# mptt-controller.net
KiCad netlist of a schematic drawn in EAGLE
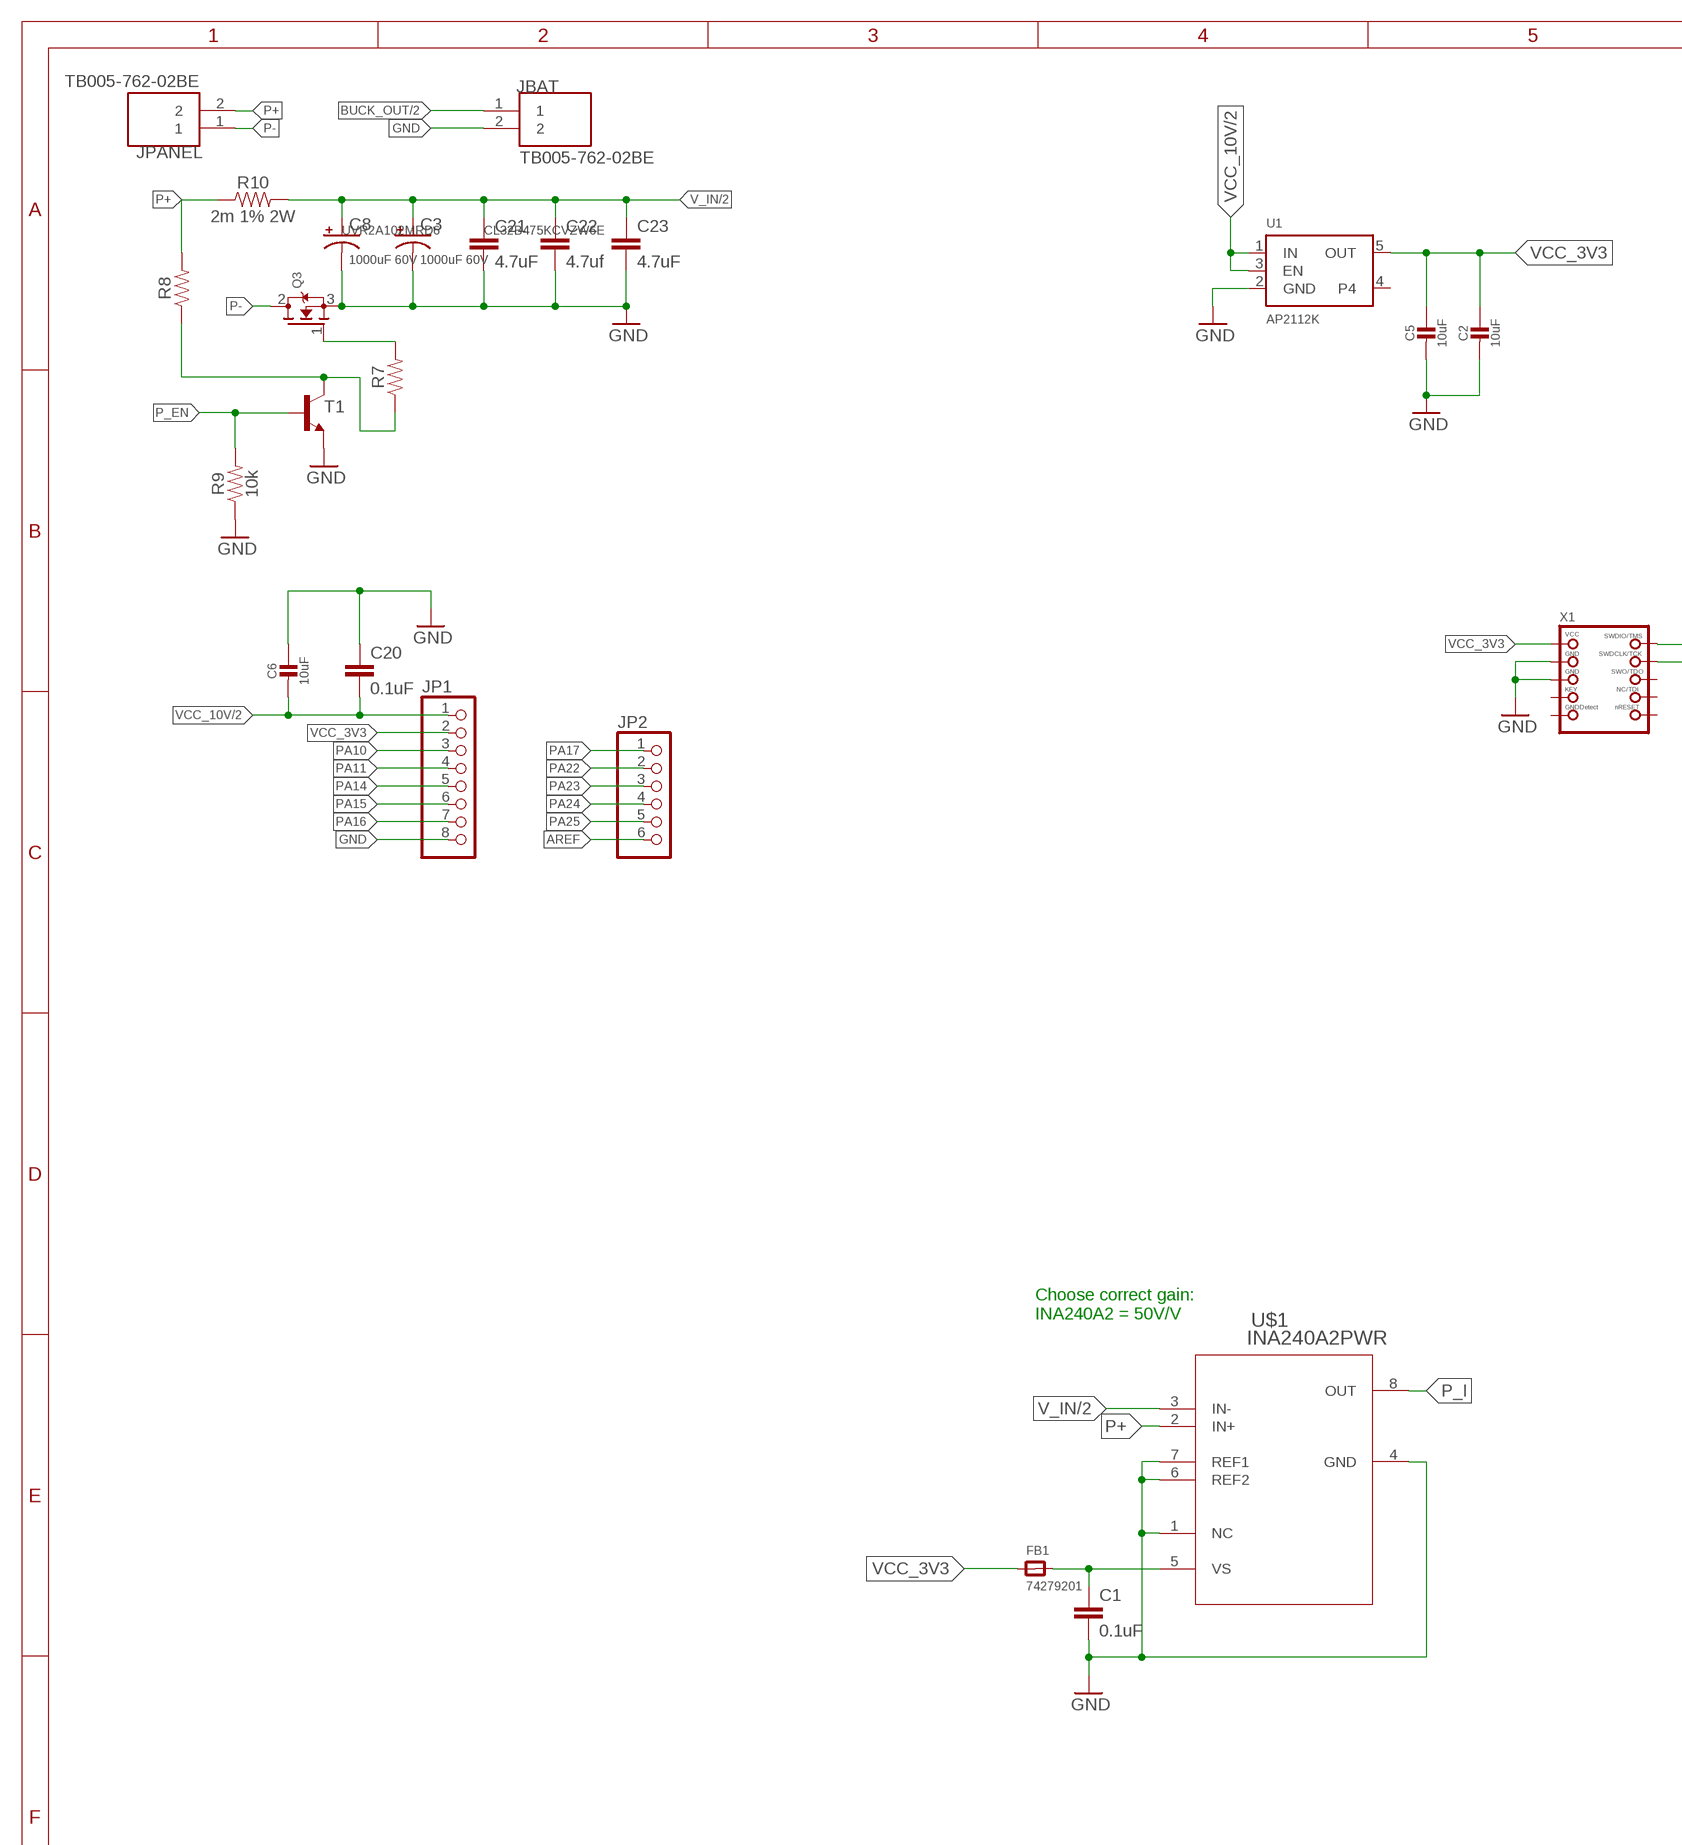
[diagram p0: schematic, sheet 1, part 1 of 2]
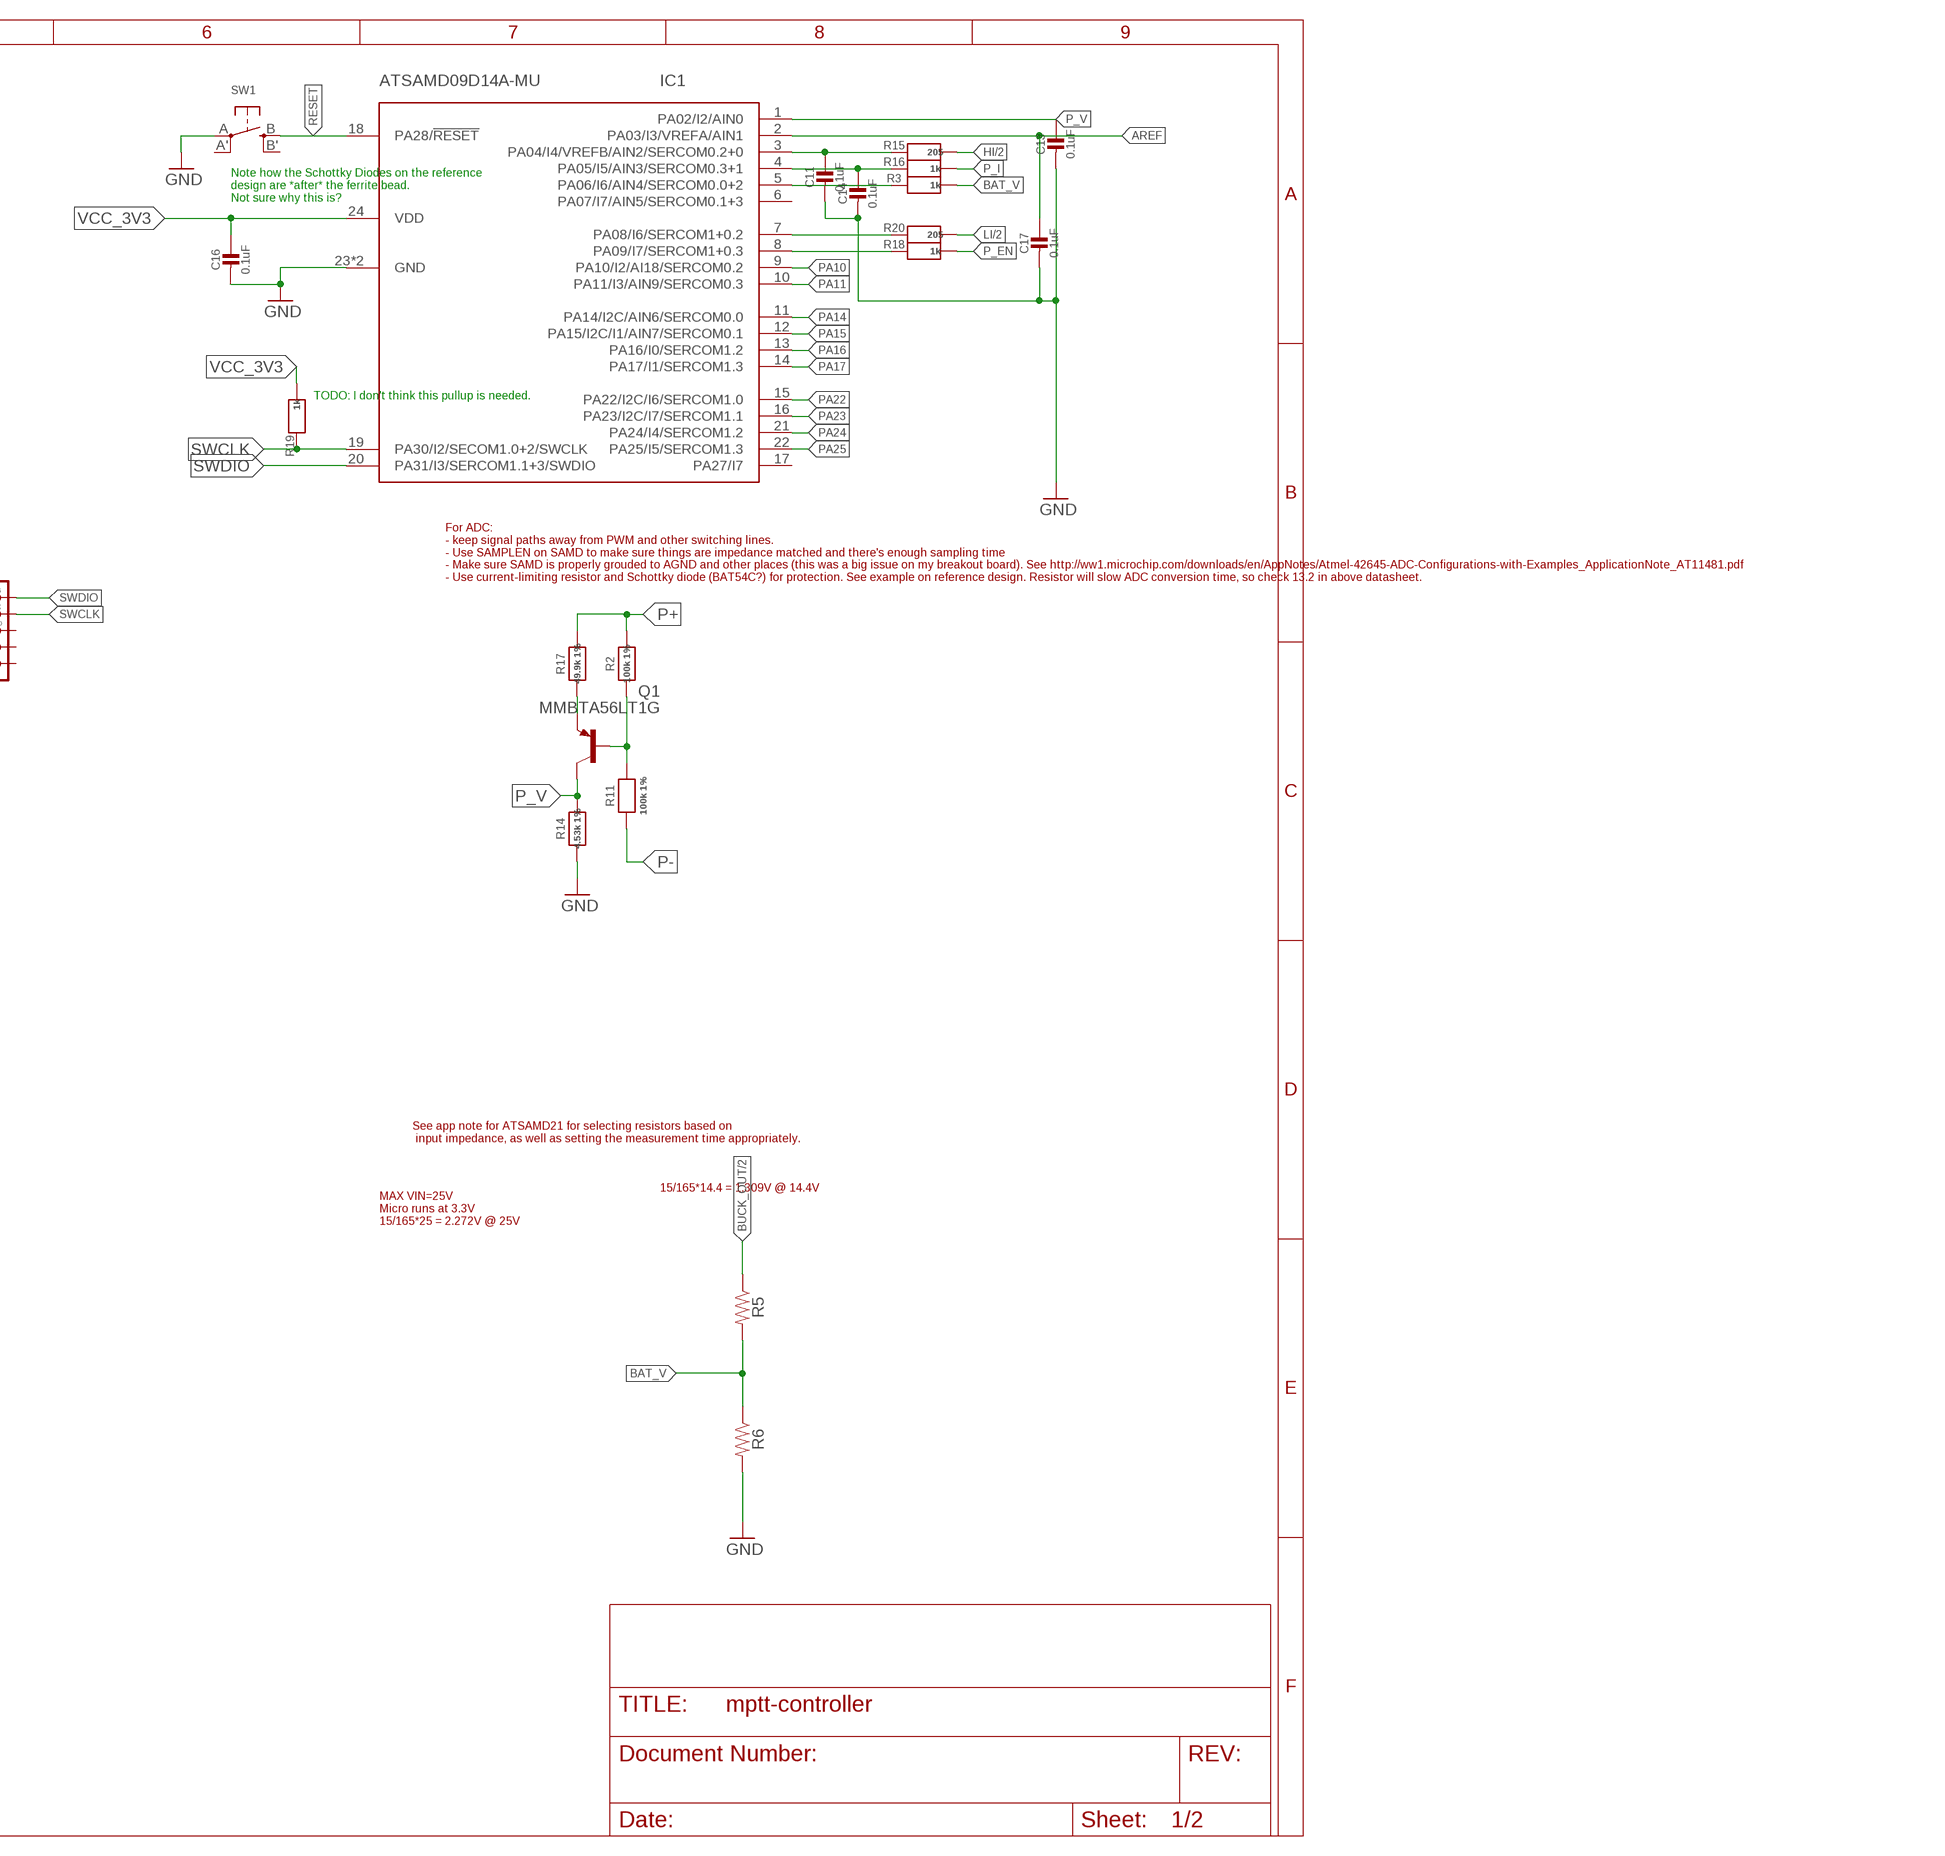
[diagram p1: schematic, sheet 1, part 2 of 2]
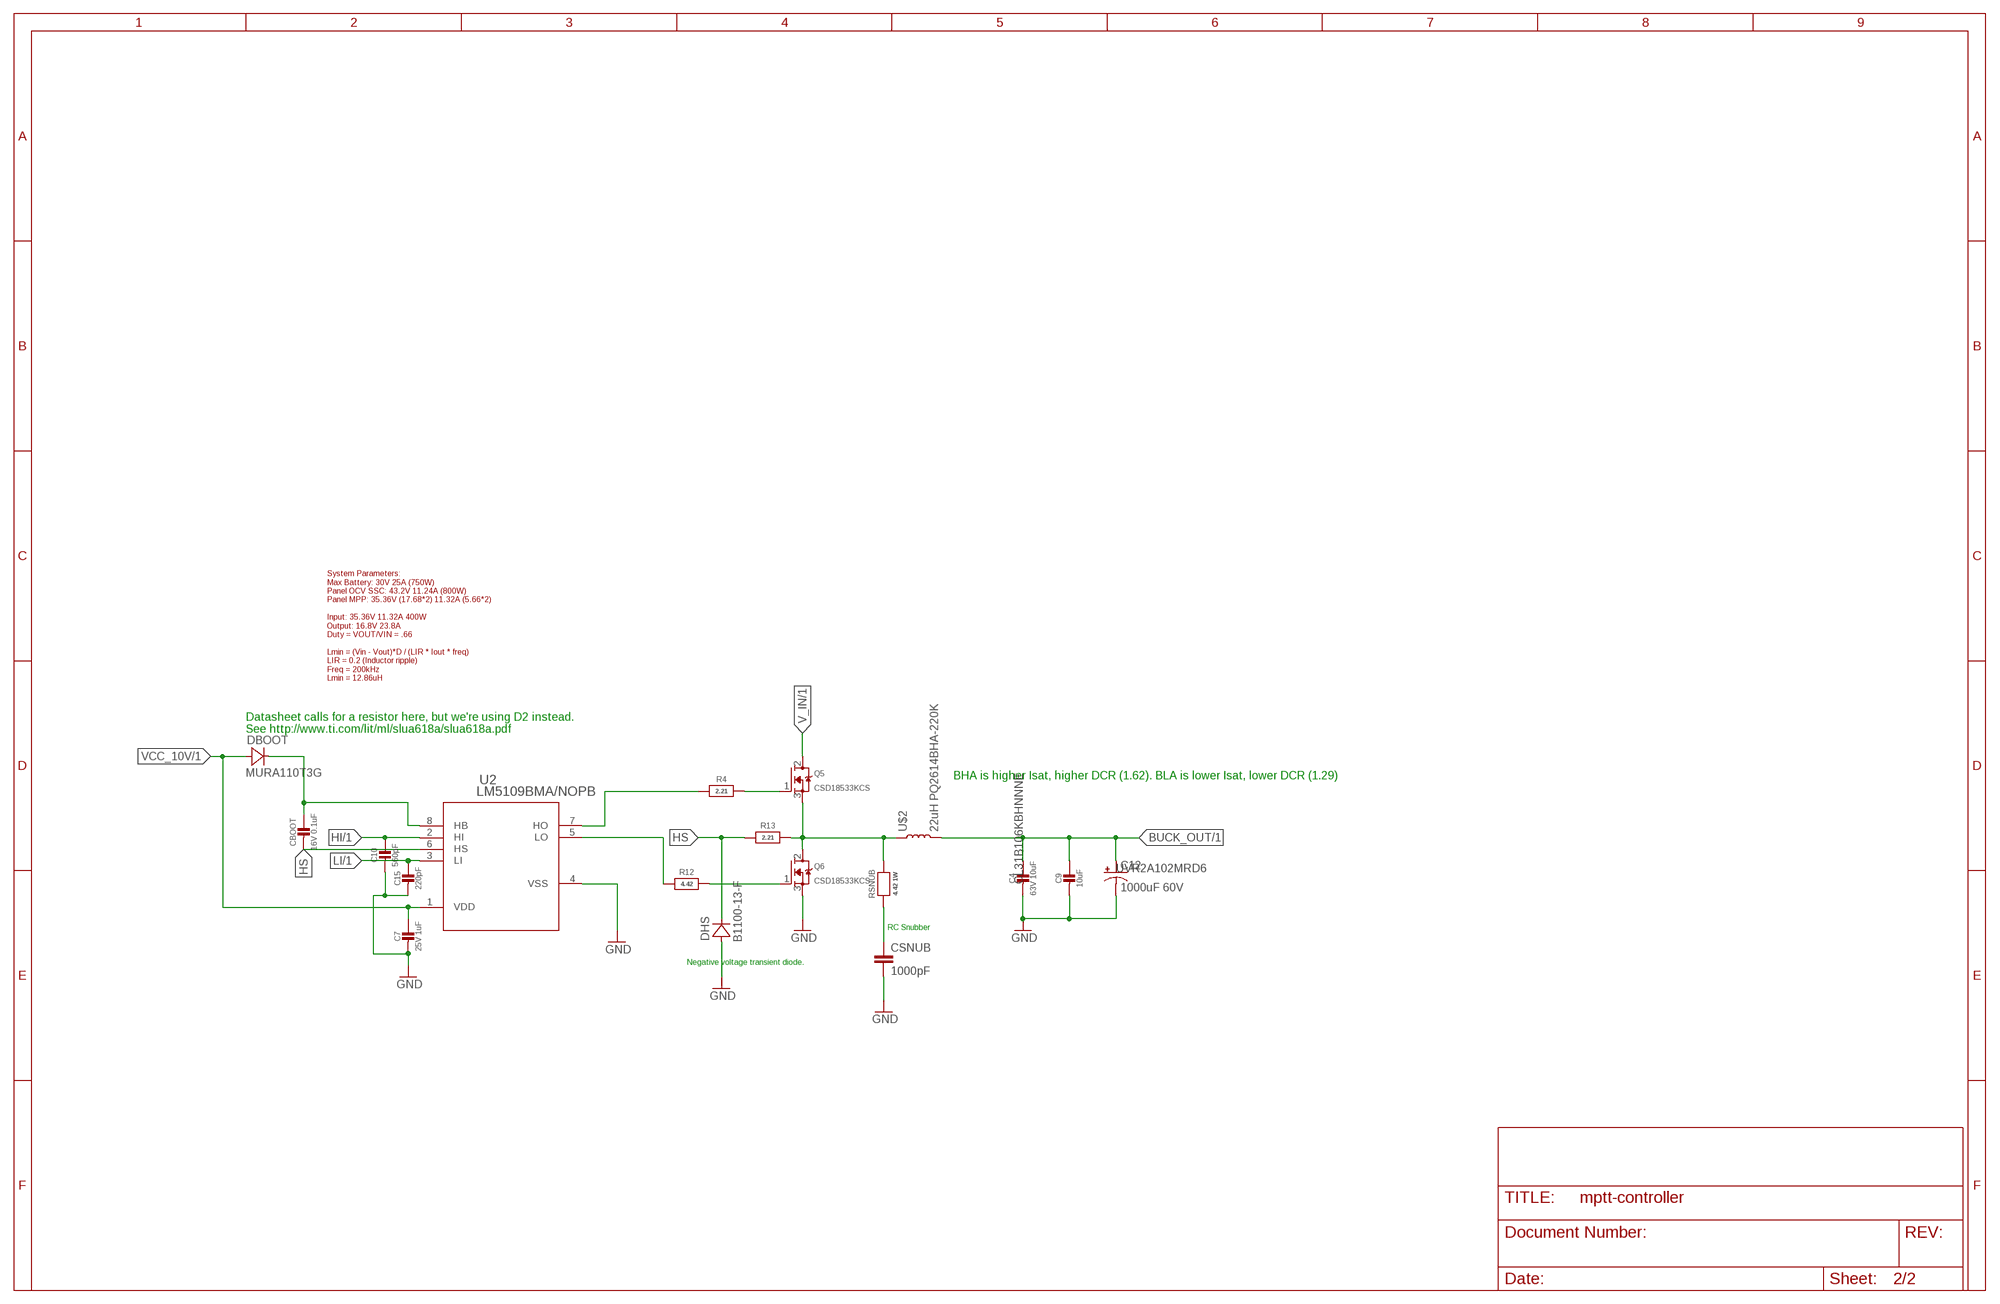
[diagram p2: schematic, sheet 2]

(export (version "E")
  (design (tool "Eeschema 10.0.6"))
  (components
    (comp (ref "C4")
      (value "63V 10uF")
      (footprint "eagle-import:_1206")
      (fields (field (name "PN") "CL31B106KBHNNNE"))
      (libsource (lib "eagle-import") (part "CAP_CERAMIC_1206"))
    )
    (comp (ref "C7")
      (value "25V 1uF")
      (footprint "eagle-import:_0805")
      (libsource (lib "eagle-import") (part "CAP_CERAMIC_0805"))
    )
    (comp (ref "C9")
      (value "10uF")
      (footprint "eagle-import:_1206")
      (libsource (lib "eagle-import") (part "CAP_CERAMIC_1206"))
    )
    (comp (ref "C10")
      (value "560pF")
      (footprint "eagle-import:_0603")
      (libsource (lib "eagle-import") (part "Adafruit Metro M0 Express_CAP_CERAMIC_0603"))
    )
    (comp (ref "C12")
      (value "1000uF 60V")
      (footprint "eagle-import:CPOL-RADIAL-1000UF-25V")
      (fields (field (name "PARTNUM") "UVR2A102MRD6"))
      (libsource (lib "eagle-import") (part "CAP_POLPTH4"))
    )
    (comp (ref "C15")
      (value "220pF")
      (footprint "eagle-import:_0603")
      (libsource (lib "eagle-import") (part "Adafruit Metro M0 Express_CAP_CERAMIC_0603"))
    )
    (comp (ref "CBOOT")
      (value "16V 0.1uF")
      (footprint "eagle-import:_0805")
      (libsource (lib "eagle-import") (part "CAP_CERAMIC_0805"))
    )
    (comp (ref "CSNUB")
      (value "1000pF")
      (footprint "eagle-import:0603-CAP")
      (libsource (lib "eagle-import") (part "0.1UF-25V(+80/-20%)(0603)"))
    )
    (comp (ref "DBOOT")
      (value "MURA110T3G")
      (footprint "eagle-import:SMA")
      (libsource (lib "eagle-import") (part "MBRA340T3"))
    )
    (comp (ref "DHS")
      (value "B1100-13-F")
      (footprint "eagle-import:SMA")
      (libsource (lib "eagle-import") (part "MBRA340T3"))
    )
    (comp (ref "Q5")
      (value "CSD18533KCS")
      (footprint "eagle-import:TO220V")
      (libsource (lib "eagle-import") (part "MOSFET-NGDS_TO220V"))
    )
    (comp (ref "Q6")
      (value "CSD18533KCS")
      (footprint "eagle-import:TO220V")
      (libsource (lib "eagle-import") (part "MOSFET-NGDS_TO220V"))
    )
    (comp (ref "R4")
      (value "2.21")
      (footprint "eagle-import:_0805")
      (libsource (lib "eagle-import") (part "Adafruit Metro M0 Express_RESISTOR_0805"))
    )
    (comp (ref "R12")
      (value "4.42")
      (footprint "eagle-import:_0805")
      (libsource (lib "eagle-import") (part "Adafruit Metro M0 Express_RESISTOR_0805"))
    )
    (comp (ref "R13")
      (value "2.21")
      (footprint "eagle-import:_0805")
      (libsource (lib "eagle-import") (part "Adafruit Metro M0 Express_RESISTOR_0805"))
    )
    (comp (ref "RSNUB")
      (value "4.42 1W")
      (footprint "eagle-import:2512")
      (libsource (lib "eagle-import") (part "Adafruit Metro M0 Express_RESISTOR2512"))
    )
    (comp (ref "U$2")
      (value "22uH PQ2614BHA-220K")
      (footprint "eagle-import:PQ2614")
      (libsource (lib "eagle-import") (part "PQ2614"))
    )
    (comp (ref "U2")
      (value "LM5109BMA/NOPB")
      (footprint "eagle-import:M08A_TEX")
      (fields (field (name "COPYRIGHT") "Copyright (C) 2018 Accelerated Designs. All rights reserved"))
      (libsource (lib "eagle-import") (part "LM5109BMA/NOPB"))
    )
    (comp (ref "C1")
      (value "0.1uF")
      (footprint "eagle-import:0603-CAP")
      (libsource (lib "eagle-import") (part "0.1UF-25V(+80/-20%)(0603)"))
    )
    (comp (ref "C2")
      (value "10uF")
      (footprint "eagle-import:_0805")
      (libsource (lib "eagle-import") (part "CAP_CERAMIC_0805"))
    )
    (comp (ref "C3")
      (value "1000uF 60V")
      (footprint "eagle-import:CPOL-RADIAL-1000UF-25V")
      (libsource (lib "eagle-import") (part "CAP_POLPTH4"))
    )
    (comp (ref "C5")
      (value "10uF")
      (footprint "eagle-import:_0805")
      (libsource (lib "eagle-import") (part "CAP_CERAMIC_0805"))
    )
    (comp (ref "C6")
      (value "10uF")
      (footprint "eagle-import:_0805")
      (libsource (lib "eagle-import") (part "CAP_CERAMIC_0805"))
    )
    (comp (ref "C8")
      (value "1000uF 60V")
      (footprint "eagle-import:CPOL-RADIAL-1000UF-25V")
      (fields (field (name "PARTNUM") "UVR2A102MRD6"))
      (libsource (lib "eagle-import") (part "CAP_POLPTH4"))
    )
    (comp (ref "C11")
      (value "0.1uF")
      (footprint "eagle-import:_0402MP")
      (libsource (lib "eagle-import") (part "CAP_CERAMIC_0402MP"))
    )
    (comp (ref "C13")
      (value "0.1uF")
      (footprint "eagle-import:_0402MP")
      (libsource (lib "eagle-import") (part "CAP_CERAMIC_0402MP"))
    )
    (comp (ref "C14")
      (value "0.1uF")
      (footprint "eagle-import:_0402MP")
      (libsource (lib "eagle-import") (part "CAP_CERAMIC_0402MP"))
    )
    (comp (ref "C16")
      (value "0.1uF")
      (footprint "eagle-import:_0402MP")
      (libsource (lib "eagle-import") (part "CAP_CERAMIC_0402MP"))
    )
    (comp (ref "C17")
      (value "0.1uF")
      (footprint "eagle-import:_0402MP")
      (libsource (lib "eagle-import") (part "CAP_CERAMIC_0402MP"))
    )
    (comp (ref "C20")
      (value "0.1uF")
      (footprint "eagle-import:0603-CAP")
      (libsource (lib "eagle-import") (part "0.1UF-25V(+80/-20%)(0603)"))
    )
    (comp (ref "C21")
      (value "4.7uF")
      (footprint "eagle-import:C1210")
      (fields (field (name "PARTNUM") "CL32B475KCVZW6E"))
      (libsource (lib "eagle-import") (part "C-EUC1210"))
    )
    (comp (ref "C22")
      (value "4.7uf")
      (footprint "eagle-import:C1210")
      (libsource (lib "eagle-import") (part "C-EUC1210"))
    )
    (comp (ref "C23")
      (value "4.7uF")
      (footprint "eagle-import:C1210")
      (libsource (lib "eagle-import") (part "C-EUC1210"))
    )
    (comp (ref "FB1")
      (value "74279201")
      (footprint "eagle-import:_0805")
      (libsource (lib "eagle-import") (part "FERRITE_0805"))
    )
    (comp (ref "IC1")
      (value "ATSAMD09D14A-MU")
      (footprint "eagle-import:QFN24_4MM")
      (libsource (lib "eagle-import") (part "ATSAMD09D14A-MU"))
    )
    (comp (ref "JBAT")
      (value "TB005-762-02BE")
      (footprint "eagle-import:CUI_TB005-762-02BE")
      (fields (field (name "MANUFACTURER") "CUI"))
      (libsource (lib "eagle-import") (part "TB005-762-02BE"))
    )
    (comp (ref "JP1")
      (value "HEADER-1X8ROUND")
      (footprint "eagle-import:1X08_ROUND")
      (libsource (lib "eagle-import") (part "HEADER-1X8ROUND"))
    )
    (comp (ref "JP2")
      (value "HEADER-1X6ROUND")
      (footprint "eagle-import:1X06_ROUND")
      (libsource (lib "eagle-import") (part "HEADER-1X6ROUND"))
    )
    (comp (ref "JPANEL")
      (value "TB005-762-02BE")
      (footprint "eagle-import:CUI_TB005-762-02BE")
      (fields (field (name "MANUFACTURER") "CUI"))
      (libsource (lib "eagle-import") (part "TB005-762-02BE"))
    )
    (comp (ref "Q1")
      (value "MMBTA56LT1G")
      (footprint "eagle-import:SOT23-BEC")
      (libsource (lib "eagle-import") (part "MMBTA92SMDLT1"))
    )
    (comp (ref "Q3")
      (value "MOSFET-NGDS_TO220V")
      (footprint "eagle-import:TO220V")
      (libsource (lib "eagle-import") (part "MOSFET-NGDS_TO220V"))
    )
    (comp (ref "R2")
      (value "100k 1%")
      (footprint "eagle-import:_0805MP")
      (libsource (lib "eagle-import") (part "Adafruit Metro M0 Express_RESISTOR_0805MP"))
    )
    (comp (ref "R3")
      (value "1k")
      (footprint "eagle-import:_0402MP")
      (libsource (lib "eagle-import") (part "RESISTOR_0402MP"))
    )
    (comp (ref "R5")
      (value "RESISTOR0603")
      (footprint "eagle-import:0603")
      (libsource (lib "eagle-import") (part "RESISTOR0603"))
    )
    (comp (ref "R6")
      (value "RESISTOR0603")
      (footprint "eagle-import:0603")
      (libsource (lib "eagle-import") (part "RESISTOR0603"))
    )
    (comp (ref "R7")
      (value "RESISTOR0603")
      (footprint "eagle-import:0603")
      (libsource (lib "eagle-import") (part "RESISTOR0603"))
    )
    (comp (ref "R8")
      (value "RESISTOR0603")
      (footprint "eagle-import:0603")
      (libsource (lib "eagle-import") (part "RESISTOR0603"))
    )
    (comp (ref "R9")
      (value "10k")
      (footprint "eagle-import:0603")
      (libsource (lib "eagle-import") (part "RESISTOR0603"))
    )
    (comp (ref "R10")
      (value "2m 1% 2W")
      (footprint "eagle-import:2512")
      (libsource (lib "eagle-import") (part "0.05OHM-2512-3W-1%"))
    )
    (comp (ref "R11")
      (value "100k 1%")
      (footprint "eagle-import:_0805MP")
      (libsource (lib "eagle-import") (part "Adafruit Metro M0 Express_RESISTOR_0805MP"))
    )
    (comp (ref "R14")
      (value "4.53k 1%")
      (footprint "eagle-import:_0805MP")
      (libsource (lib "eagle-import") (part "Adafruit Metro M0 Express_RESISTOR_0805MP"))
    )
    (comp (ref "R15")
      (value "205")
      (footprint "eagle-import:_0402MP")
      (libsource (lib "eagle-import") (part "RESISTOR_0402MP"))
    )
    (comp (ref "R16")
      (value "1k")
      (footprint "eagle-import:_0402MP")
      (libsource (lib "eagle-import") (part "RESISTOR_0402MP"))
    )
    (comp (ref "R17")
      (value "49.9k 1%")
      (footprint "eagle-import:_0805MP")
      (libsource (lib "eagle-import") (part "Adafruit Metro M0 Express_RESISTOR_0805MP"))
    )
    (comp (ref "R18")
      (value "1k")
      (footprint "eagle-import:_0402MP")
      (libsource (lib "eagle-import") (part "RESISTOR_0402MP"))
    )
    (comp (ref "R19")
      (value "1k")
      (footprint "eagle-import:_0402MP")
      (libsource (lib "eagle-import") (part "RESISTOR_0402MP"))
    )
    (comp (ref "R20")
      (value "205")
      (footprint "eagle-import:_0402MP")
      (libsource (lib "eagle-import") (part "RESISTOR_0402MP"))
    )
    (comp (ref "SW1")
      (value "SWITCH_TACT_SMT4.6X2.8")
      (footprint "eagle-import:BTN_KMR2_4.6X2.8")
      (libsource (lib "eagle-import") (part "SWITCH_TACT_SMT4.6X2.8"))
    )
    (comp (ref "T1")
      (value "MMBT3904LT1-NPN-SOT23-BEC")
      (footprint "eagle-import:SOT23-BEC")
      (libsource (lib "eagle-import") (part "-NPN-SOT23-BECMMBT3904LT1"))
    )
    (comp (ref "U$1")
      (value "INA240A2PWR")
      (footprint "eagle-import:PW0008A_N")
      (libsource (lib "eagle-import") (part "INA240"))
    )
    (comp (ref "U1")
      (value "AP2112K")
      (footprint "eagle-import:SOT23-5")
      (libsource (lib "eagle-import") (part "VREG_SOT23-5"))
    )
    (comp (ref "X1")
      (value "JTAG-CORTEXBOX")
      (footprint "eagle-import:2X05_1.27MM_BOX_NOPOSTS")
      (libsource (lib "eagle-import") (part "JTAG-CORTEXBOX"))
    )
  )
  (nets
    (net (code "1") (name "AREF") (class "Default")
      (node (ref "C17") (pin "1") (pinfunction "1_1") (pintype "passive"))
      (node (ref "IC1") (pin "2") (pinfunction "PA03/I3/VREFA/AIN1_2") (pintype "bidirectional"))
      (node (ref "JP2") (pin "6") (pinfunction "6_6") (pintype "passive"))
    )
    (net (code "2") (name "BAT_V") (class "Default")
      (node (ref "R3") (pin "2") (pinfunction "2_2") (pintype "passive"))
      (node (ref "R5") (pin "2") (pinfunction "2_2") (pintype "passive"))
      (node (ref "R6") (pin "1") (pinfunction "1_1") (pintype "passive"))
    )
    (net (code "3") (name "BUCK_OUT") (class "Default")
      (node (ref "C12") (pin "+") (pinfunction "+_+") (pintype "passive"))
      (node (ref "C4") (pin "1") (pinfunction "1_1") (pintype "passive"))
      (node (ref "C9") (pin "1") (pinfunction "1_1") (pintype "passive"))
      (node (ref "JBAT") (pin "1") (pinfunction "1_1") (pintype "passive"))
      (node (ref "R5") (pin "1") (pinfunction "1_1") (pintype "passive"))
      (node (ref "U$2") (pin "P2") (pinfunction "2_P2") (pintype "passive"))
    )
    (net (code "4") (name "GND") (class "Default")
      (node (ref "C1") (pin "2") (pinfunction "2_2") (pintype "passive"))
      (node (ref "C10") (pin "2") (pinfunction "2_2") (pintype "passive"))
      (node (ref "C11") (pin "2") (pinfunction "2_2") (pintype "passive"))
      (node (ref "C12") (pin "-") (pinfunction "-_-") (pintype "passive"))
      (node (ref "C13") (pin "2") (pinfunction "2_2") (pintype "passive"))
      (node (ref "C14") (pin "2") (pinfunction "2_2") (pintype "passive"))
      (node (ref "C15") (pin "2") (pinfunction "2_2") (pintype "passive"))
      (node (ref "C16") (pin "2") (pinfunction "2_2") (pintype "passive"))
      (node (ref "C17") (pin "2") (pinfunction "2_2") (pintype "passive"))
      (node (ref "C2") (pin "2") (pinfunction "2_2") (pintype "passive"))
      (node (ref "C20") (pin "1") (pinfunction "1_1") (pintype "passive"))
      (node (ref "C21") (pin "2") (pinfunction "2_2") (pintype "passive"))
      (node (ref "C22") (pin "2") (pinfunction "2_2") (pintype "passive"))
      (node (ref "C23") (pin "2") (pinfunction "2_2") (pintype "passive"))
      (node (ref "C3") (pin "-") (pinfunction "-_-") (pintype "passive"))
      (node (ref "C4") (pin "2") (pinfunction "2_2") (pintype "passive"))
      (node (ref "C5") (pin "2") (pinfunction "2_2") (pintype "passive"))
      (node (ref "C6") (pin "1") (pinfunction "1_1") (pintype "passive"))
      (node (ref "C7") (pin "2") (pinfunction "2_2") (pintype "passive"))
      (node (ref "C8") (pin "-") (pinfunction "-_-") (pintype "passive"))
      (node (ref "C9") (pin "2") (pinfunction "2_2") (pintype "passive"))
      (node (ref "CSNUB") (pin "2") (pinfunction "2_2") (pintype "passive"))
      (node (ref "DHS") (pin "A") (pinfunction "A_A") (pintype "passive"))
      (node (ref "IC1") (pin "23") (pinfunction "GND_23") (pintype "power_in"))
      (node (ref "IC1") (pin "THERM") (pinfunction "GND_THERM") (pintype "power_in"))
      (node (ref "JBAT") (pin "2") (pinfunction "2_2") (pintype "passive"))
      (node (ref "JP1") (pin "8") (pinfunction "8_8") (pintype "passive"))
      (node (ref "Q3") (pin "3") (pinfunction "S_3") (pintype "bidirectional"))
      (node (ref "Q6") (pin "3") (pinfunction "S_3") (pintype "bidirectional"))
      (node (ref "R14") (pin "1") (pinfunction "1_1") (pintype "passive"))
      (node (ref "R6") (pin "2") (pinfunction "2_2") (pintype "passive"))
      (node (ref "R9") (pin "1") (pinfunction "1_1") (pintype "passive"))
      (node (ref "SW1") (pin "A") (pinfunction "P_A") (pintype "passive"))
      (node (ref "T1") (pin "E") (pinfunction "E_E") (pintype "passive"))
      (node (ref "U$1") (pin "1") (pinfunction "NC_1") (pintype "passive"))
      (node (ref "U$1") (pin "4") (pinfunction "GND_4") (pintype "power_in"))
      (node (ref "U$1") (pin "6") (pinfunction "REF2_6") (pintype "input"))
      (node (ref "U$1") (pin "7") (pinfunction "REF1_7") (pintype "input"))
      (node (ref "U1") (pin "2") (pinfunction "GND_2") (pintype "power_in"))
      (node (ref "U2") (pin "4") (pinfunction "VSS_4") (pintype "power_in"))
      (node (ref "X1") (pin "3") (pinfunction "GND_3") (pintype "power_in"))
      (node (ref "X1") (pin "5") (pinfunction "GND_5") (pintype "power_in"))
    )
    (net (code "5") (name "HI") (class "Default")
      (node (ref "C10") (pin "1") (pinfunction "1_1") (pintype "passive"))
      (node (ref "R15") (pin "2") (pinfunction "2_2") (pintype "passive"))
      (node (ref "U2") (pin "2") (pinfunction "HI_2") (pintype "input"))
    )
    (net (code "6") (name "HS") (class "Default")
      (node (ref "CBOOT") (pin "2") (pinfunction "2_2") (pintype "passive"))
      (node (ref "DHS") (pin "C") (pinfunction "C_C") (pintype "passive"))
      (node (ref "R13") (pin "1") (pinfunction "1_1") (pintype "passive"))
      (node (ref "U2") (pin "6") (pinfunction "HS_6") (pintype "input"))
    )
    (net (code "7") (name "LI") (class "Default")
      (node (ref "C15") (pin "1") (pinfunction "1_1") (pintype "passive"))
      (node (ref "R20") (pin "2") (pinfunction "2_2") (pintype "passive"))
      (node (ref "U2") (pin "3") (pinfunction "LI_3") (pintype "input"))
    )
    (net (code "8") (name "Net-(CSNUB-Pad1)") (class "Default")
      (node (ref "CSNUB") (pin "1") (pinfunction "1_1") (pintype "passive"))
      (node (ref "RSNUB") (pin "1") (pinfunction "1_1") (pintype "passive"))
    )
    (net (code "9") (name "Net-(FB1-P$2)") (class "Default")
      (node (ref "C1") (pin "1") (pinfunction "1_1") (pintype "passive"))
      (node (ref "FB1") (pin "2") (pinfunction "P$2_2") (pintype "passive"))
      (node (ref "U$1") (pin "5") (pinfunction "VS_5") (pintype "power_in"))
    )
    (net (code "10") (name "Net-(IC1-PA04{slash}I4{slash}VREFB{slash}AIN2{slash}SERCOM0.2+0)") (class "Default")
      (node (ref "C11") (pin "1") (pinfunction "1_1") (pintype "passive"))
      (node (ref "IC1") (pin "3") (pinfunction "PA04/I4/VREFB/AIN2/SERCOM0.2+0_3") (pintype "bidirectional"))
      (node (ref "R15") (pin "1") (pinfunction "1_1") (pintype "passive"))
    )
    (net (code "11") (name "Net-(IC1-PA05{slash}I5{slash}AIN3{slash}SERCOM0.3+1)") (class "Default")
      (node (ref "C14") (pin "1") (pinfunction "1_1") (pintype "passive"))
      (node (ref "IC1") (pin "4") (pinfunction "PA05/I5/AIN3/SERCOM0.3+1_4") (pintype "bidirectional"))
      (node (ref "R16") (pin "1") (pinfunction "1_1") (pintype "passive"))
    )
    (net (code "12") (name "Net-(IC1-PA06{slash}I6{slash}AIN4{slash}SERCOM0.0+2)") (class "Default")
      (node (ref "IC1") (pin "5") (pinfunction "PA06/I6/AIN4/SERCOM0.0+2_5") (pintype "bidirectional"))
      (node (ref "R3") (pin "1") (pinfunction "1_1") (pintype "passive"))
    )
    (net (code "13") (name "Net-(IC1-PA08{slash}I6{slash}SERCOM1+0.2)") (class "Default")
      (node (ref "IC1") (pin "7") (pinfunction "PA08/I6/SERCOM1+0.2_7") (pintype "bidirectional"))
      (node (ref "R20") (pin "1") (pinfunction "1_1") (pintype "passive"))
    )
    (net (code "14") (name "Net-(IC1-PA09{slash}I7{slash}SERCOM1+0.3)") (class "Default")
      (node (ref "IC1") (pin "8") (pinfunction "PA09/I7/SERCOM1+0.3_8") (pintype "bidirectional"))
      (node (ref "R18") (pin "1") (pinfunction "1_1") (pintype "passive"))
    )
    (net (code "15") (name "Net-(Q1-PadB)") (class "Default")
      (node (ref "Q1") (pin "B") (pinfunction "B_B") (pintype "passive"))
      (node (ref "R11") (pin "2") (pinfunction "2_2") (pintype "passive"))
      (node (ref "R2") (pin "1") (pinfunction "1_1") (pintype "passive"))
    )
    (net (code "16") (name "Net-(Q1-PadE)") (class "Default")
      (node (ref "Q1") (pin "E") (pinfunction "E_E") (pintype "passive"))
      (node (ref "R17") (pin "1") (pinfunction "1_1") (pintype "passive"))
    )
    (net (code "17") (name "Net-(Q3-G)") (class "Default")
      (node (ref "Q3") (pin "1") (pinfunction "G_1") (pintype "bidirectional"))
      (node (ref "R7") (pin "2") (pinfunction "2_2") (pintype "passive"))
    )
    (net (code "18") (name "Net-(Q5-G)") (class "Default")
      (node (ref "Q5") (pin "1") (pinfunction "G_1") (pintype "bidirectional"))
      (node (ref "R4") (pin "2") (pinfunction "2_2") (pintype "passive"))
    )
    (net (code "19") (name "Net-(Q5-S)") (class "Default")
      (node (ref "Q5") (pin "3") (pinfunction "S_3") (pintype "bidirectional"))
      (node (ref "Q6") (pin "2") (pinfunction "D_2") (pintype "bidirectional"))
      (node (ref "R13") (pin "2") (pinfunction "2_2") (pintype "passive"))
      (node (ref "RSNUB") (pin "2") (pinfunction "2_2") (pintype "passive"))
      (node (ref "U$2") (pin "P1") (pinfunction "1_P1") (pintype "passive"))
    )
    (net (code "20") (name "Net-(Q6-G)") (class "Default")
      (node (ref "Q6") (pin "1") (pinfunction "G_1") (pintype "bidirectional"))
      (node (ref "R12") (pin "2") (pinfunction "2_2") (pintype "passive"))
    )
    (net (code "21") (name "Net-(R7-Pad1)") (class "Default")
      (node (ref "R7") (pin "1") (pinfunction "1_1") (pintype "passive"))
      (node (ref "R8") (pin "1") (pinfunction "1_1") (pintype "passive"))
      (node (ref "T1") (pin "C") (pinfunction "C_C") (pintype "passive"))
    )
    (net (code "22") (name "Net-(U2-HB)") (class "Default")
      (node (ref "CBOOT") (pin "1") (pinfunction "1_1") (pintype "passive"))
      (node (ref "DBOOT") (pin "C") (pinfunction "C_C") (pintype "passive"))
      (node (ref "U2") (pin "8") (pinfunction "HB_8") (pintype "input"))
    )
    (net (code "23") (name "Net-(U2-HO)") (class "Default")
      (node (ref "R4") (pin "1") (pinfunction "1_1") (pintype "passive"))
      (node (ref "U2") (pin "7") (pinfunction "HO_7") (pintype "output"))
    )
    (net (code "24") (name "Net-(U2-LO)") (class "Default")
      (node (ref "R12") (pin "1") (pinfunction "1_1") (pintype "passive"))
      (node (ref "U2") (pin "5") (pinfunction "LO_5") (pintype "output"))
    )
    (net (code "25") (name "P+") (class "Default")
      (node (ref "JPANEL") (pin "2") (pinfunction "2_2") (pintype "passive"))
      (node (ref "R10") (pin "P$1") (pinfunction "1_P$1") (pintype "passive"))
      (node (ref "R17") (pin "2") (pinfunction "2_2") (pintype "passive"))
      (node (ref "R2") (pin "2") (pinfunction "2_2") (pintype "passive"))
      (node (ref "R8") (pin "2") (pinfunction "2_2") (pintype "passive"))
      (node (ref "U$1") (pin "2") (pinfunction "IN+_2") (pintype "input"))
    )
    (net (code "26") (name "P-") (class "Default")
      (node (ref "JPANEL") (pin "1") (pinfunction "1_1") (pintype "passive"))
      (node (ref "Q3") (pin "2") (pinfunction "D_2") (pintype "bidirectional"))
      (node (ref "R11") (pin "1") (pinfunction "1_1") (pintype "passive"))
    )
    (net (code "27") (name "PA10") (class "Default")
      (node (ref "IC1") (pin "9") (pinfunction "PA10/I2/AI18/SERCOM0.2_9") (pintype "bidirectional"))
      (node (ref "JP1") (pin "3") (pinfunction "3_3") (pintype "passive"))
    )
    (net (code "28") (name "PA11") (class "Default")
      (node (ref "IC1") (pin "10") (pinfunction "PA11/I3/AIN9/SERCOM0.3_10") (pintype "bidirectional"))
      (node (ref "JP1") (pin "4") (pinfunction "4_4") (pintype "passive"))
    )
    (net (code "29") (name "PA14") (class "Default")
      (node (ref "IC1") (pin "11") (pinfunction "PA14/I2C/AIN6/SERCOM0.0_11") (pintype "bidirectional"))
      (node (ref "JP1") (pin "5") (pinfunction "5_5") (pintype "passive"))
    )
    (net (code "30") (name "PA15") (class "Default")
      (node (ref "IC1") (pin "12") (pinfunction "PA15/I2C/I1/AIN7/SERCOM0.1_12") (pintype "bidirectional"))
      (node (ref "JP1") (pin "6") (pinfunction "6_6") (pintype "passive"))
    )
    (net (code "31") (name "PA16") (class "Default")
      (node (ref "IC1") (pin "13") (pinfunction "PA16/I0/SERCOM1.2_13") (pintype "bidirectional"))
      (node (ref "JP1") (pin "7") (pinfunction "7_7") (pintype "passive"))
    )
    (net (code "32") (name "PA17") (class "Default")
      (node (ref "IC1") (pin "14") (pinfunction "PA17/I1/SERCOM1.3_14") (pintype "bidirectional"))
      (node (ref "JP2") (pin "1") (pinfunction "1_1") (pintype "passive"))
    )
    (net (code "33") (name "PA22") (class "Default")
      (node (ref "IC1") (pin "15") (pinfunction "PA22/I2C/I6/SERCOM1.0_15") (pintype "bidirectional"))
      (node (ref "JP2") (pin "2") (pinfunction "2_2") (pintype "passive"))
    )
    (net (code "34") (name "PA23") (class "Default")
      (node (ref "IC1") (pin "16") (pinfunction "PA23/I2C/I7/SERCOM1.1_16") (pintype "bidirectional"))
      (node (ref "JP2") (pin "3") (pinfunction "3_3") (pintype "passive"))
    )
    (net (code "35") (name "PA24") (class "Default")
      (node (ref "IC1") (pin "21") (pinfunction "PA24/I4/SERCOM1.2_21") (pintype "bidirectional"))
      (node (ref "JP2") (pin "4") (pinfunction "4_4") (pintype "passive"))
    )
    (net (code "36") (name "PA25") (class "Default")
      (node (ref "IC1") (pin "22") (pinfunction "PA25/I5/SERCOM1.3_22") (pintype "bidirectional"))
      (node (ref "JP2") (pin "5") (pinfunction "5_5") (pintype "passive"))
    )
    (net (code "37") (name "P_EN") (class "Default")
      (node (ref "R18") (pin "2") (pinfunction "2_2") (pintype "passive"))
      (node (ref "R9") (pin "2") (pinfunction "2_2") (pintype "passive"))
      (node (ref "T1") (pin "B") (pinfunction "B_B") (pintype "passive"))
    )
    (net (code "38") (name "P_I") (class "Default")
      (node (ref "R16") (pin "2") (pinfunction "2_2") (pintype "passive"))
      (node (ref "U$1") (pin "8") (pinfunction "OUT_8") (pintype "output"))
    )
    (net (code "39") (name "P_V") (class "Default")
      (node (ref "C13") (pin "1") (pinfunction "1_1") (pintype "passive"))
      (node (ref "IC1") (pin "1") (pinfunction "PA02/I2/AIN0_1") (pintype "bidirectional"))
      (node (ref "Q1") (pin "C") (pinfunction "C_C") (pintype "passive"))
      (node (ref "R14") (pin "2") (pinfunction "2_2") (pintype "passive"))
    )
    (net (code "40") (name "RESET") (class "Default")
      (node (ref "IC1") (pin "18") (pinfunction "PA28/~{RESET}_18") (pintype "bidirectional"))
      (node (ref "SW1") (pin "B") (pinfunction "S_B") (pintype "passive"))
    )
    (net (code "41") (name "SWCLK") (class "Default")
      (node (ref "IC1") (pin "19") (pinfunction "PA30/I2/SECOM1.0+2/SWCLK_19") (pintype "bidirectional"))
      (node (ref "R19") (pin "1") (pinfunction "1_1") (pintype "passive"))
      (node (ref "X1") (pin "4") (pinfunction "SWDCLK_4") (pintype "bidirectional"))
    )
    (net (code "42") (name "SWDIO") (class "Default")
      (node (ref "IC1") (pin "20") (pinfunction "PA31/I3/SERCOM1.1+3/SWDIO_20") (pintype "bidirectional"))
      (node (ref "X1") (pin "2") (pinfunction "SWDIO_2") (pintype "bidirectional"))
    )
    (net (code "43") (name "VCC_3V3") (class "Default")
      (node (ref "C16") (pin "1") (pinfunction "1_1") (pintype "passive"))
      (node (ref "C2") (pin "1") (pinfunction "1_1") (pintype "passive"))
      (node (ref "C5") (pin "1") (pinfunction "1_1") (pintype "passive"))
      (node (ref "FB1") (pin "1") (pinfunction "P$1_1") (pintype "passive"))
      (node (ref "IC1") (pin "24") (pinfunction "VDD_24") (pintype "power_in"))
      (node (ref "JP1") (pin "2") (pinfunction "2_2") (pintype "passive"))
      (node (ref "R19") (pin "2") (pinfunction "2_2") (pintype "passive"))
      (node (ref "U1") (pin "5") (pinfunction "OUT_5") (pintype "power_in"))
      (node (ref "X1") (pin "1") (pinfunction "VCC_1") (pintype "power_in"))
    )
    (net (code "44") (name "VCC_10V") (class "Default")
      (node (ref "C20") (pin "2") (pinfunction "2_2") (pintype "passive"))
      (node (ref "C6") (pin "2") (pinfunction "2_2") (pintype "passive"))
      (node (ref "C7") (pin "1") (pinfunction "1_1") (pintype "passive"))
      (node (ref "DBOOT") (pin "A") (pinfunction "A_A") (pintype "passive"))
      (node (ref "JP1") (pin "1") (pinfunction "1_1") (pintype "passive"))
      (node (ref "U1") (pin "1") (pinfunction "IN_1") (pintype "power_in"))
      (node (ref "U1") (pin "3") (pinfunction "EN_3") (pintype "input"))
      (node (ref "U2") (pin "1") (pinfunction "VDD_1") (pintype "power_in"))
    )
    (net (code "45") (name "V_IN") (class "Default")
      (node (ref "C21") (pin "1") (pinfunction "1_1") (pintype "passive"))
      (node (ref "C22") (pin "1") (pinfunction "1_1") (pintype "passive"))
      (node (ref "C23") (pin "1") (pinfunction "1_1") (pintype "passive"))
      (node (ref "C3") (pin "+") (pinfunction "+_+") (pintype "passive"))
      (node (ref "C8") (pin "+") (pinfunction "+_+") (pintype "passive"))
      (node (ref "Q5") (pin "2") (pinfunction "D_2") (pintype "bidirectional"))
      (node (ref "R10") (pin "P$2") (pinfunction "2_P$2") (pintype "passive"))
      (node (ref "U$1") (pin "3") (pinfunction "IN-_3") (pintype "input"))
    )
    (net (code "46") (name "unconnected-(IC1-PA07{slash}I7{slash}AIN5{slash}SERCOM0.1+3-Pad6)") (class "Default")
      (node (ref "IC1") (pin "6") (pinfunction "PA07/I7/AIN5/SERCOM0.1+3_6") (pintype "bidirectional"))
    )
    (net (code "47") (name "unconnected-(IC1-PA27{slash}I7-Pad17)") (class "Default")
      (node (ref "IC1") (pin "17") (pinfunction "PA27/I7_17") (pintype "bidirectional"))
    )
    (net (code "48") (name "unconnected-(SW1-P1-PadA')") (class "Default")
      (node (ref "SW1") (pin "A'") (pinfunction "P1_A'") (pintype "passive"))
    )
    (net (code "49") (name "unconnected-(SW1-S1-PadB')") (class "Default")
      (node (ref "SW1") (pin "B'") (pinfunction "S1_B'") (pintype "passive"))
    )
    (net (code "50") (name "unconnected-(U1-P4-Pad4)") (class "Default")
      (node (ref "U1") (pin "4") (pinfunction "P4_4") (pintype "bidirectional"))
    )
    (net (code "51") (name "unconnected-(X1-GNDDETECT-Pad9)") (class "Default")
      (node (ref "X1") (pin "9") (pinfunction "GNDDETECT_9") (pintype "bidirectional"))
    )
    (net (code "52") (name "unconnected-(X1-KEY-Pad7)") (class "Default")
      (node (ref "X1") (pin "7") (pinfunction "KEY_7") (pintype "bidirectional"))
    )
    (net (code "53") (name "unconnected-(X1-NRESET-Pad10)") (class "Default")
      (node (ref "X1") (pin "10") (pinfunction "NRESET_10") (pintype "bidirectional"))
    )
    (net (code "54") (name "unconnected-(X1-SWO-Pad6)") (class "Default")
      (node (ref "X1") (pin "6") (pinfunction "SWO_6") (pintype "bidirectional"))
    )
    (net (code "55") (name "unconnected-(X1-TDI-Pad8)") (class "Default")
      (node (ref "X1") (pin "8") (pinfunction "TDI_8") (pintype "bidirectional"))
    )
  )
)
